# 5V_Power_Supply.net
KiCad netlist of a schematic drawn in Altium Designer
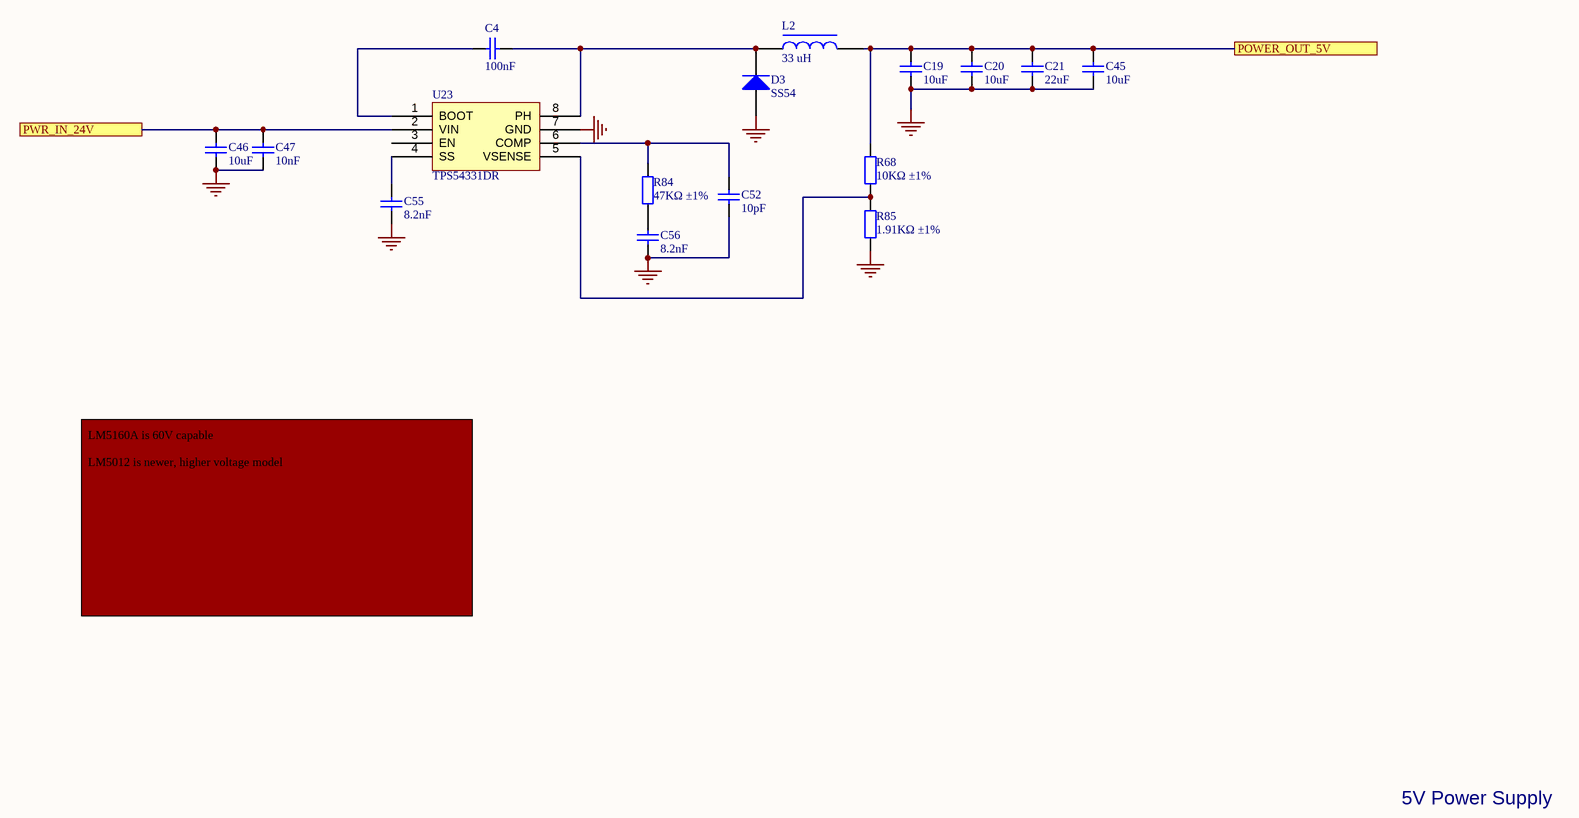
[diagram p0: 5V_Power_Supply.SchDoc]

(export (version "E")
  (design (tool "Eeschema 10.0.6"))
  (components
    (comp (ref "C4")
      (value "100nF")
      (footprint "0603_C")
      (description "Chip capacitors")
      (fields (field (name "MANUFACTURER") "YAGEO") (field (name "PARTNUMBER") "CC0603KRX7R9BB104"))
      (libsource (lib "Cap") (part "0603 100nF (104) 10% 50V"))
    )
    (comp (ref "C19")
      (value "10uF")
      (footprint "1206_C")
      (description "Chip capacitors")
      (fields
        (field (name "MANUFACTURER") "Samsung Electro-Mechanics")
        (field (name "PARTNUMBER") "CL31A106KBHNNNE")
      )
      (libsource (lib "Cap") (part "1206 10uF (106) 10% 50V"))
    )
    (comp (ref "C20")
      (value "10uF")
      (footprint "1206_C")
      (description "Chip capacitors")
      (fields
        (field (name "MANUFACTURER") "Samsung Electro-Mechanics")
        (field (name "PARTNUMBER") "CL31A106KBHNNNE")
      )
      (libsource (lib "Cap") (part "1206 10uF (106) 10% 50V"))
    )
    (comp (ref "C21")
      (value "22uF")
      (footprint "0805_C")
      (description "Chip capacitors")
      (fields
        (field (name "MANUFACTURER") "Samsung Electro-Mechanics")
        (field (name "PARTNUMBER") "CL21A226MAQNNNE")
      )
      (libsource (lib "Cap") (part "0805 22uF (226) 20% 25V"))
    )
    (comp (ref "C45")
      (value "10uF")
      (footprint "1206_C")
      (description "Chip capacitors")
      (fields
        (field (name "MANUFACTURER") "Samsung Electro-Mechanics")
        (field (name "PARTNUMBER") "CL31A106KBHNNNE")
      )
      (libsource (lib "Cap") (part "1206 10uF (106) 10% 50V"))
    )
    (comp (ref "C46")
      (value "10uF")
      (footprint "1206_C")
      (description "Chip capacitors")
      (fields
        (field (name "MANUFACTURER") "Samsung Electro-Mechanics")
        (field (name "PARTNUMBER") "CL31A106KBHNNNE")
      )
      (libsource (lib "Cap") (part "1206 10uF (106) 10% 50V"))
    )
    (comp (ref "C47")
      (value "10nF")
      (footprint "0603_C")
      (description "Chip capacitors")
      (fields
        (field (name "MANUFACTURER") "Guangdong Fenghua Advanced Tech")
        (field (name "PARTNUMBER") "0603B103K500NT")
      )
      (libsource (lib "Cap") (part "0603 10nF (103) 10% 50V"))
    )
    (comp (ref "C52")
      (value "10pF")
      (footprint "0603_C")
      (description "Chip capacitors")
      (fields
        (field (name "MANUFACTURER") "Samsung Electro-Mechanics")
        (field (name "PARTNUMBER") "CL10C100JB8NNNC")
      )
      (libsource (lib "Cap") (part "0603 10pF (100) 5% 50V"))
    )
    (comp (ref "C55")
      (value "8.2nF")
      (footprint "0603_C")
      (description "Chip capacitors")
      (fields
        (field (name "MANUFACTURER") "Samsung Electro-Mechanics")
        (field (name "PARTNUMBER") "CL10B822KB8NNNC")
      )
      (libsource (lib "Cap") (part "0603 8.2nF (822) 10% 50V"))
    )
    (comp (ref "C56")
      (value "8.2nF")
      (footprint "0603_C")
      (description "Chip capacitors")
      (fields
        (field (name "MANUFACTURER") "Samsung Electro-Mechanics")
        (field (name "PARTNUMBER") "CL10B822KB8NNNC")
      )
      (libsource (lib "Cap") (part "0603 8.2nF (822) 10% 50V"))
    )
    (comp (ref "D3")
      (value "SS54")
      (footprint "SMA(DO-214AC)_S1")
      (description "40V 5A 550mV@5A")
      (libsource (lib "Diode") (part "SMA(DO-214AC) SS54"))
    )
    (comp (ref "L2")
      (value "33 uH")
      (footprint "INDPM7366X300N")
      (description "33uH ±20% 2A 270mΩ SMD,6.6x7.3x3.0mm Power Inductors RoHS")
      (libsource (lib "PrintNC_GRBLHAL_Breakout") (part "1206 10uH 10%"))
    )
    (comp (ref "R68")
      (value "10KΩ ±1%")
      (footprint "0603_R")
      (description "Chip resistor")
      (fields (field (name "MANUFACTURER") "Uniroyal Elec") (field (name "PARTNUMBER") "0603WAF1002T5E"))
      (libsource (lib "RES") (part "0603 10K (1002) 1%"))
    )
    (comp (ref "R84")
      (value "47KΩ ±1%")
      (footprint "0603_R")
      (description "Chip resistor")
      (fields (field (name "MANUFACTURER") "Uniroyal Elec") (field (name "PARTNUMBER") "0603WAF4702T5E"))
      (libsource (lib "RES") (part "0603 47K (4702) 1%"))
    )
    (comp (ref "R85")
      (value "1.91KΩ ±1%")
      (footprint "0603_R")
      (description "Chip resistor")
      (fields (field (name "MANUFACTURER") "Uniroyal Elec") (field (name "PARTNUMBER") "0603WAF1911T5E"))
      (libsource (lib "RES") (part "0603 2K (2001) 1%"))
    )
    (comp (ref "U23")
      (value "TPS54331DR")
      (footprint "Miscellaneous Devices LC:SOIC-8_150mil")
      (description "Switching Voltage Regulators 3A 28V In Step Down SWIFT DC/DC Cnvrtr")
      (libsource (lib "PrintNC_GRBLHAL_Breakout") (part "TPS54331DR_[C9865]"))
    )
  )
  (nets
    (net (code "1") (name "/POWER_OUT_5V") (class "Default")
      (node (ref "C19") (pin "2") (pinfunction "2_2") (pintype "passive"))
      (node (ref "C20") (pin "2") (pinfunction "2_2") (pintype "passive"))
      (node (ref "C21") (pin "2") (pinfunction "2_2") (pintype "passive"))
      (node (ref "C45") (pin "2") (pinfunction "2_2") (pintype "passive"))
      (node (ref "L2") (pin "2") (pinfunction "2_2") (pintype "passive"))
      (node (ref "R68") (pin "2") (pinfunction "2_2") (pintype "passive"))
    )
    (net (code "2") (name "/PWR_IN_24V") (class "Default")
      (node (ref "C46") (pin "2") (pinfunction "2_2") (pintype "passive"))
      (node (ref "C47") (pin "2") (pinfunction "2_2") (pintype "passive"))
      (node (ref "U23") (pin "2") (pinfunction "VIN_2") (pintype "passive"))
    )
    (net (code "3") (name "GND") (class "Default")
      (node (ref "C19") (pin "1") (pinfunction "1_1") (pintype "passive"))
      (node (ref "C20") (pin "1") (pinfunction "1_1") (pintype "passive"))
      (node (ref "C21") (pin "1") (pinfunction "1_1") (pintype "passive"))
      (node (ref "C45") (pin "1") (pinfunction "1_1") (pintype "passive"))
      (node (ref "C46") (pin "1") (pinfunction "1_1") (pintype "passive"))
      (node (ref "C47") (pin "1") (pinfunction "1_1") (pintype "passive"))
      (node (ref "C52") (pin "1") (pinfunction "1_1") (pintype "passive"))
      (node (ref "C55") (pin "1") (pinfunction "1_1") (pintype "passive"))
      (node (ref "C56") (pin "1") (pinfunction "1_1") (pintype "passive"))
      (node (ref "D3") (pin "1") (pinfunction "A_1") (pintype "passive"))
      (node (ref "R85") (pin "1") (pinfunction "1_1") (pintype "passive"))
      (node (ref "U23") (pin "7") (pinfunction "GND_7") (pintype "passive"))
    )
    (net (code "4") (name "Net-(C56-Pad2)") (class "Default")
      (node (ref "C56") (pin "2") (pinfunction "2_2") (pintype "passive"))
      (node (ref "R84") (pin "1") (pinfunction "1_1") (pintype "passive"))
    )
    (net (code "5") (name "Net-(D3-K)") (class "Default")
      (node (ref "C4") (pin "2") (pinfunction "2_2") (pintype "passive"))
      (node (ref "D3") (pin "2") (pinfunction "K_2") (pintype "passive"))
      (node (ref "L2") (pin "1") (pinfunction "1_1") (pintype "passive"))
      (node (ref "U23") (pin "8") (pinfunction "PH_8") (pintype "passive"))
    )
    (net (code "6") (name "Net-(U23-BOOT)") (class "Default")
      (node (ref "C4") (pin "1") (pinfunction "1_1") (pintype "passive"))
      (node (ref "U23") (pin "1") (pinfunction "BOOT_1") (pintype "passive"))
    )
    (net (code "7") (name "Net-(U23-COMP)") (class "Default")
      (node (ref "C52") (pin "2") (pinfunction "2_2") (pintype "passive"))
      (node (ref "R84") (pin "2") (pinfunction "2_2") (pintype "passive"))
      (node (ref "U23") (pin "6") (pinfunction "COMP_6") (pintype "passive"))
    )
    (net (code "8") (name "Net-(U23-SS)") (class "Default")
      (node (ref "C55") (pin "2") (pinfunction "2_2") (pintype "passive"))
      (node (ref "U23") (pin "4") (pinfunction "SS_4") (pintype "passive"))
    )
    (net (code "9") (name "Net-(U23-VSENSE)") (class "Default")
      (node (ref "R68") (pin "1") (pinfunction "1_1") (pintype "passive"))
      (node (ref "R85") (pin "2") (pinfunction "2_2") (pintype "passive"))
      (node (ref "U23") (pin "5") (pinfunction "VSENSE_5") (pintype "passive"))
    )
    (net (code "10") (name "unconnected-(U23-EN-Pad3)") (class "Default")
      (node (ref "U23") (pin "3") (pinfunction "EN_3") (pintype "passive"))
    )
  )
)
